# SmartWatch-V2-Sensors.net
KiCad netlist of a schematic drawn in Altium Designer
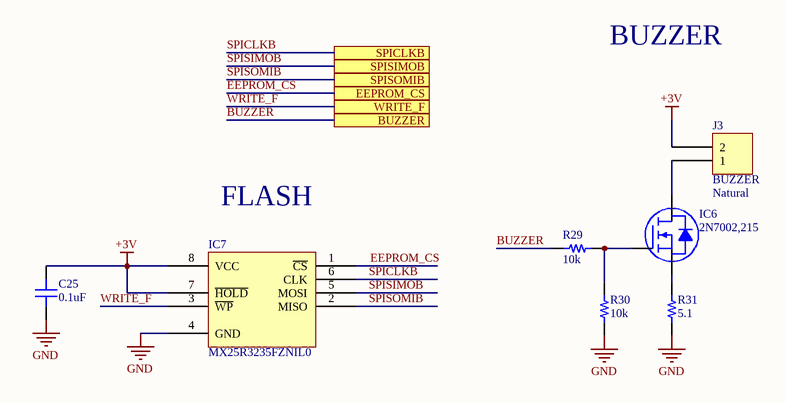
[diagram p0: SmartWatch-V2-Sensors.SchDoc]

(export (version "E")
  (design (tool "Eeschema 10.0.6"))
  (components
    (comp (ref "C25")
      (value "0.1uF")
      (footprint "CAP 0402/1005")
      (description "CAP CER 0.1UF 16V X7R 0402")
      (fields
        (field (name "PART NUMBER") "C1005X7R1C104K050BC")
        (field (name "MANUFACTURER") "TDK Corporation")
      )
      (libsource (lib "Celestial Library Database") (part "Capacitor"))
    )
    (comp (ref "IC6")
      (value "2N7002,215")
      (footprint "NXP SOT-23-3 TO-236AB")
      (description "MOSFET N-CH 60V 300MA SOT-23")
      (fields (field (name "MANUFACTURER") "NXP Semiconductors"))
      (libsource (lib "Celestial Library Database") (part "NXP MOSFET N-CH SOT-23-3"))
    )
    (comp (ref "IC7")
      (value "MX25R3235FZNIL0")
      (footprint "SPANSION WSON-8 6x5MM")
      (description "IC FLASH MEM 16MB SPI CMOS 8WSON")
      (fields (field (name "PART NUMBER") "S25FL116K0XNFI011") (field (name "MANUFACTURER") "Spansion"))
      (libsource (lib "Celestial Library Database") (part "SPANSION FLASH SPI 8PIN"))
    )
    (comp (ref "J3")
      (value "BUZZER")
      (footprint "ST-025BH")
      (description "CONN HEADER XH TOP 2POS 2.5MM")
      (fields
        (field (name "PART NUMBER") "B2B-XH-A(LF)(SN)")
        (field (name "COLOUR") "Natural")
        (field (name "MANUFACTURER") "JST Sales America Inc.")
      )
      (libsource (lib "Celestial Library Database") (part "2 Pin"))
    )
    (comp (ref "R29")
      (value "10k")
      (footprint "RES 0402/1005")
      (description "RES SMD 10K OHM 0.5% 1/16W 0402")
      (fields
        (field (name "PART NUMBER") "ERA-2AED103X")
        (field (name "MANUFACTURER") "Panasonic Electronic Components")
      )
      (libsource (lib "Celestial Library Database") (part "Resistor"))
    )
    (comp (ref "R30")
      (value "10k")
      (footprint "RES 0603/1608")
      (description "RES SMD 10K OHM 0.1% 1/10W 0603")
      (fields
        (field (name "PART NUMBER") "ERA-3AEB103V")
        (field (name "MANUFACTURER") "Panasonic Electronic Components")
      )
      (libsource (lib "Celestial Library Database") (part "Resistor"))
    )
    (comp (ref "R31")
      (value "5.1")
      (footprint "RES 0603/1608")
      (description "RES SMD 5.1 OHM 5% 1/10W 0603")
      (fields
        (field (name "PART NUMBER") "ERJ-3GEYJ5R1V")
        (field (name "MANUFACTURER") "Panasonic Electronic Components")
      )
      (libsource (lib "Celestial Library Database") (part "Resistor"))
    )
  )
  (nets
    (net (code "1") (name "+3V") (class "Default")
      (node (ref "C25") (pin "2") (pinfunction "2_2") (pintype "passive"))
      (node (ref "IC7") (pin "7") (pinfunction "~{HOLD}_7") (pintype "passive"))
      (node (ref "IC7") (pin "8") (pinfunction "VCC_8") (pintype "passive"))
      (node (ref "J3") (pin "2") (pinfunction "2_2") (pintype "passive"))
    )
    (net (code "2") (name "/BUZZER") (class "Default")
      (node (ref "R29") (pin "2") (pinfunction "2_2") (pintype "passive"))
    )
    (net (code "3") (name "/EEPROM_CS") (class "Default")
      (node (ref "IC7") (pin "1") (pinfunction "~{CS}_1") (pintype "passive"))
    )
    (net (code "4") (name "/SPICLKB") (class "Default")
      (node (ref "IC7") (pin "6") (pinfunction "CLK_6") (pintype "passive"))
    )
    (net (code "5") (name "/SPISIMOB") (class "Default")
      (node (ref "IC7") (pin "5") (pinfunction "MOSI_5") (pintype "passive"))
    )
    (net (code "6") (name "/SPISOMIB") (class "Default")
      (node (ref "IC7") (pin "2") (pinfunction "MISO_2") (pintype "passive"))
    )
    (net (code "7") (name "/WRITE_F") (class "Default")
      (node (ref "IC7") (pin "3") (pinfunction "~{WP}_3") (pintype "passive"))
    )
    (net (code "8") (name "GND") (class "Default")
      (node (ref "C25") (pin "1") (pinfunction "1_1") (pintype "passive"))
      (node (ref "IC7") (pin "4") (pinfunction "GND_4") (pintype "passive"))
      (node (ref "R30") (pin "1") (pinfunction "1_1") (pintype "passive"))
      (node (ref "R31") (pin "1") (pinfunction "1_1") (pintype "passive"))
    )
    (net (code "9") (name "Net-(IC6-D)") (class "Default")
      (node (ref "IC6") (pin "2") (pinfunction "D_2") (pintype "passive"))
      (node (ref "J3") (pin "1") (pinfunction "1_1") (pintype "passive"))
    )
    (net (code "10") (name "Net-(IC6-G)") (class "Default")
      (node (ref "IC6") (pin "1") (pinfunction "G_1") (pintype "passive"))
      (node (ref "R29") (pin "1") (pinfunction "1_1") (pintype "passive"))
      (node (ref "R30") (pin "2") (pinfunction "2_2") (pintype "passive"))
    )
    (net (code "11") (name "Net-(IC6-S)") (class "Default")
      (node (ref "IC6") (pin "3") (pinfunction "S_3") (pintype "passive"))
      (node (ref "R31") (pin "2") (pinfunction "2_2") (pintype "passive"))
    )
  )
)
